# 08_EXP_CN.net
KiCad netlist of a schematic drawn in Altium Designer
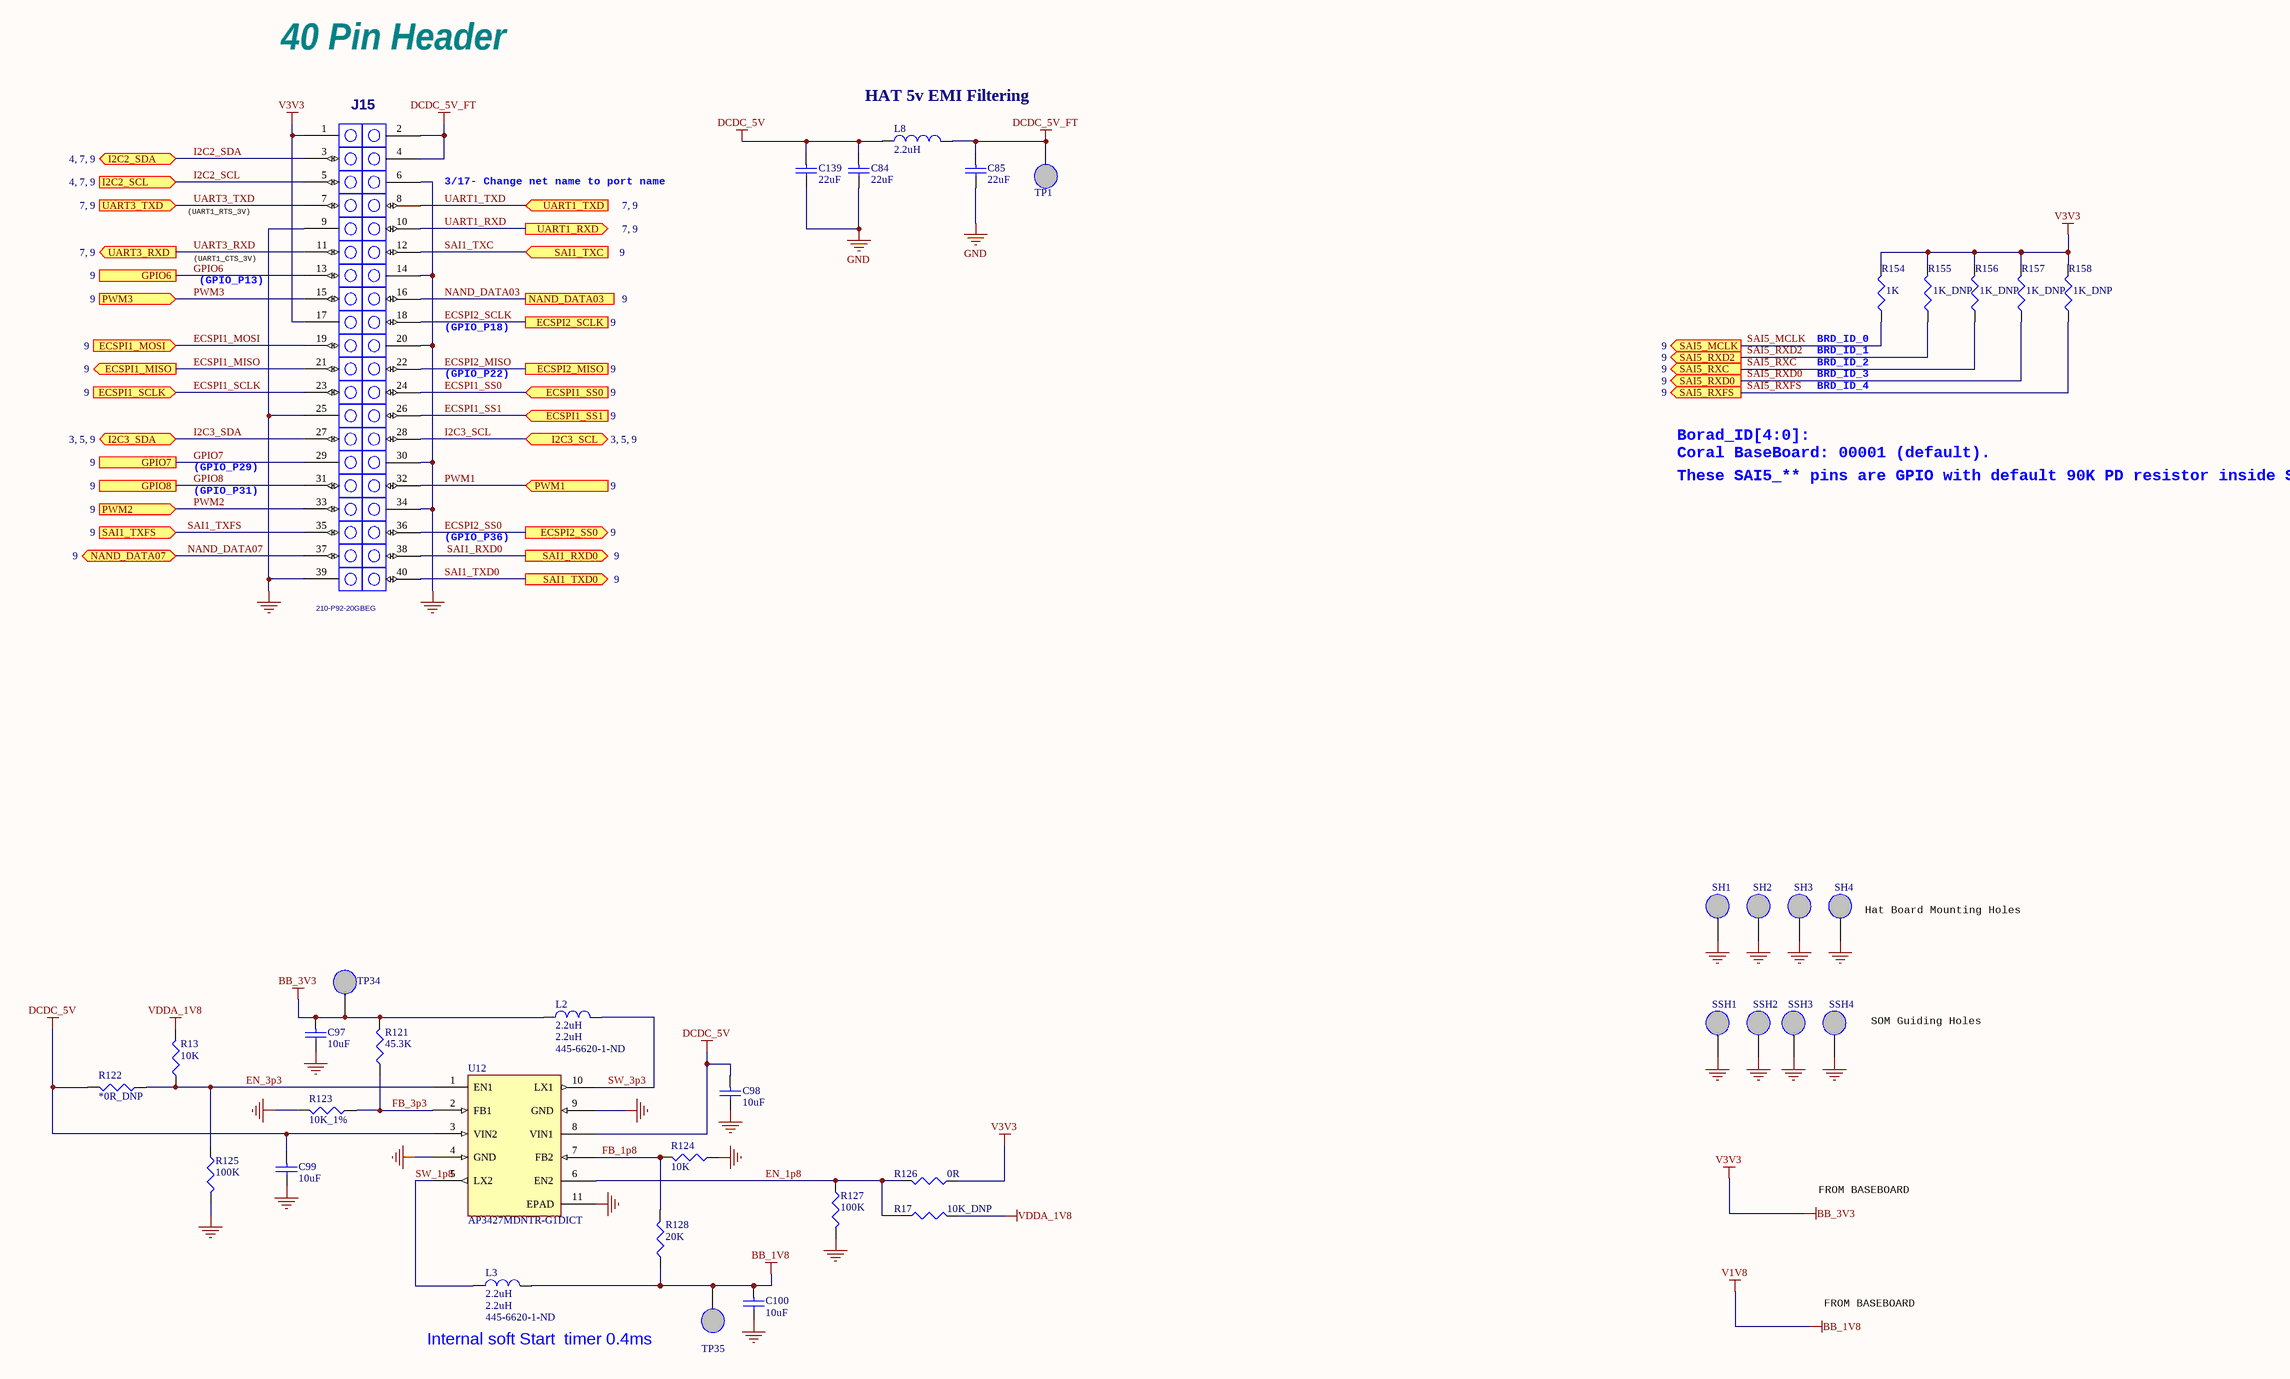
[diagram p0: 08_EXP_CN.SchDoc]

(export (version "E")
  (design (tool "Eeschema 10.0.6"))
  (components
    (comp (ref "C84")
      (value "22uF")
      (footprint "0603")
      (description "CAP CER 22UF 6.3V 10% X5R 0603")
      (fields (field (name "MPN") "CL10A226KQ8NRNE") (field (name "Comment") "22uF/10V"))
      (libsource (lib "links") (part "CAP_0603_22uF"))
    )
    (comp (ref "C85")
      (value "22uF")
      (footprint "0603")
      (description "CAP CER 22UF 6.3V 10% X5R 0603")
      (fields (field (name "MPN") "CL10A226KQ8NRNE") (field (name "Comment") "22uF/10V"))
      (libsource (lib "links") (part "CAP_0603_22uF"))
    )
    (comp (ref "C97")
      (value "10uF")
      (footprint "0402")
      (description "CAP CER 10UF 10V 20% X5R 0402")
      (fields (field (name "MPN") "CL05A106MP5NUNC") (field (name "Comment") "10uF/10V"))
      (libsource (lib "links") (part "CAP_0402_10uF"))
    )
    (comp (ref "C98")
      (value "10uF")
      (footprint "0402")
      (description "CAP CER 10UF 10V 20% X5R 0402")
      (fields (field (name "MPN") "CL05A106MP5NUNC") (field (name "Comment") "10uF/10V"))
      (libsource (lib "links") (part "CAP_0402_10uF"))
    )
    (comp (ref "C99")
      (value "10uF")
      (footprint "0402")
      (description "CAP CER 10UF 10V 20% X5R 0402")
      (fields (field (name "MPN") "CL05A106MP5NUNC") (field (name "Comment") "10uF/10V"))
      (libsource (lib "links") (part "CAP_0402_10uF"))
    )
    (comp (ref "C100")
      (value "10uF")
      (footprint "0402")
      (description "CAP CER 10UF 10V 20% X5R 0402")
      (fields (field (name "MPN") "CL05A106MP5NUNC") (field (name "Comment") "10uF/10V"))
      (libsource (lib "links") (part "CAP_0402_10uF"))
    )
    (comp (ref "C139")
      (value "22uF")
      (footprint "0603")
      (description "CAP CER 22UF 6.3V 10% X5R 0603")
      (fields (field (name "MPN") "CL10A226KQ8NRNE") (field (name "Comment") "22uF/10V"))
      (libsource (lib "links") (part "CAP_0603_22uF"))
    )
    (comp (ref "J15")
      (value "210-P92-20GBEG")
      (footprint "HTSW-120-41-G-D")
      (description "SOCKET 2X20 100-MIL STRAIGHT SMT")
      (libsource (lib "SpacePark") (part "CONN_HEADER_20x2_SMT"))
    )
    (comp (ref "L2")
      (value "2.2uH")
      (footprint "INDC2016X12L")
      (description "FIXED IND 2.2UH 1.05A 195 MOHM SMD")
      (fields
        (field (name "ALTIUM_VALUE") "2.2uH")
        (field (name "SUPPLIER PART NUMBER 1") "445-6620-1-ND")
        (field (name "MPN") "VLS201612ET-2R2M")
      )
      (libsource (lib "links") (part "INDUCTOR_VLS201612ET-2R2M"))
    )
    (comp (ref "L3")
      (value "2.2uH")
      (footprint "INDC2016X12L")
      (description "FIXED IND 2.2UH 1.05A 195 MOHM SMD")
      (fields
        (field (name "ALTIUM_VALUE") "2.2uH")
        (field (name "SUPPLIER PART NUMBER 1") "445-6620-1-ND")
        (field (name "MPN") "VLS201612ET-2R2M")
      )
      (libsource (lib "links") (part "INDUCTOR_VLS201612ET-2R2M"))
    )
    (comp (ref "L8")
      (value "2.2uH")
      (footprint "0805_PADS")
      (description "2.2?Inductor 800mA 200 mOhm Max 0805 (2012 Metric)")
      (fields (field (name "MPN") "SDTR20120H-2R2MS"))
      (libsource (lib "SpacePark") (part "INDUCTOR_2.2uH_800mA_0805"))
    )
    (comp (ref "R13")
      (value "10K")
      (footprint "0201")
      (description "RES SMD 10K OHM JUMPER 1/20W  0201")
      (fields (field (name "MPN") "ERJ-1GEF103C") (field (name "Comment") "10K_DNP"))
      (libsource (lib "links") (part "R_0201_10K"))
    )
    (comp (ref "R17")
      (value "10K_DNP")
      (footprint "0201")
      (description "RES SMD 10K OHM JUMPER 1/20W  0201")
      (fields (field (name "MPN") "ERJ-1GEF103C"))
      (libsource (lib "links") (part "R_0201_10K"))
    )
    (comp (ref "R121")
      (value "45.3K")
      (footprint "0201")
      (description "RES CHIP 45.3K 1/20W +-1%(0201)")
      (fields (field (name "MPN") "RM02FTN4532"))
      (libsource (lib "links") (part "R_0201_453K"))
    )
    (comp (ref "R122")
      (value "*0R_DNP")
      (footprint "0201")
      (description "RES SMD 0.0OHM JUMPER 1/20W 0201")
      (fields (field (name "MPN") "ERJ-1GN0R00C") (field (name "Comment") "0R"))
      (libsource (lib "links") (part "R_0201_0"))
    )
    (comp (ref "R123")
      (value "10K_1%")
      (footprint "0201")
      (description "RES SMD 10K OHM JUMPER 1/20W  0201")
      (fields (field (name "MPN") "ERJ-1GEF103C") (field (name "Comment") "10K"))
      (libsource (lib "links") (part "R_0201_10K"))
    )
    (comp (ref "R124")
      (value "10K")
      (footprint "0201")
      (description "RES SMD 10K OHM JUMPER 1/20W  0201")
      (fields (field (name "MPN") "ERJ-1GEF103C"))
      (libsource (lib "links") (part "R_0201_10K"))
    )
    (comp (ref "R125")
      (value "100K")
      (footprint "0201")
      (description "RES SMD 100K OHM JUMPER 1/20W  0201")
      (fields (field (name "MPN") "ERJ-1GEF1003C"))
      (libsource (lib "links") (part "R_0201_100K"))
    )
    (comp (ref "R126")
      (value "0R")
      (footprint "0201")
      (description "RES SMD 0.0OHM JUMPER 1/20W 0201")
      (fields (field (name "MPN") "ERJ-1GN0R00C"))
      (libsource (lib "links") (part "R_0201_0"))
    )
    (comp (ref "R127")
      (value "100K")
      (footprint "0201")
      (description "RES SMD 100K OHM JUMPER 1/20W  0201")
      (fields (field (name "MPN") "ERJ-1GEF1003C"))
      (libsource (lib "links") (part "R_0201_100K"))
    )
    (comp (ref "R128")
      (value "20K")
      (footprint "0201")
      (description "RES SMD 20K OHM 1% 1/20W 0201")
      (fields (field (name "MPN") "ERJ-1GEF2002C"))
      (libsource (lib "links") (part "R_0201_20K"))
    )
    (comp (ref "R154")
      (value "1K")
      (footprint "0201")
      (description "RES SMD 1K OHM 1% 1/20W 0201")
      (fields (field (name "MPN") "ERJ-1GEF1001C") (field (name "Comment") "1K/1%"))
      (libsource (lib "links") (part "R_0201_1K"))
    )
    (comp (ref "R155")
      (value "1K_DNP")
      (footprint "0201")
      (description "RES SMD 1K OHM 1% 1/20W 0201")
      (fields (field (name "MPN") "ERJ-1GEF1001C"))
      (libsource (lib "links") (part "R_0201_1K"))
    )
    (comp (ref "R156")
      (value "1K_DNP")
      (footprint "0201")
      (description "RES SMD 1K OHM 1% 1/20W 0201")
      (fields (field (name "MPN") "ERJ-1GEF1001C"))
      (libsource (lib "links") (part "R_0201_1K"))
    )
    (comp (ref "R157")
      (value "1K_DNP")
      (footprint "0201")
      (description "RES SMD 1K OHM 1% 1/20W 0201")
      (fields (field (name "MPN") "ERJ-1GEF1001C"))
      (libsource (lib "links") (part "R_0201_1K"))
    )
    (comp (ref "R158")
      (value "1K_DNP")
      (footprint "0201")
      (description "RES SMD 1K OHM 1% 1/20W 0201")
      (fields (field (name "MPN") "ERJ-1GEF1001C"))
      (libsource (lib "links") (part "R_0201_1K"))
    )
    (comp (ref "SH1")
      (value "TP NM")
      (footprint "hole236-110")
      (description "TEST POIN")
      (libsource (lib "links") (part "TP"))
    )
    (comp (ref "SH2")
      (value "TP NM")
      (footprint "hole236-110")
      (description "TEST POIN")
      (libsource (lib "links") (part "TP"))
    )
    (comp (ref "SH3")
      (value "TP NM")
      (footprint "hole236-110")
      (description "TEST POIN")
      (libsource (lib "links") (part "TP"))
    )
    (comp (ref "SH4")
      (value "TP NM")
      (footprint "hole236-110")
      (description "TEST POIN")
      (libsource (lib "links") (part "TP"))
    )
    (comp (ref "SSH1") (value "stand-off") (footprint "hole120-80") (libsource (lib "links") (part "TP")))
    (comp (ref "SSH2") (value "stand-off") (footprint "hole120-80") (libsource (lib "links") (part "TP")))
    (comp (ref "SSH3") (value "stand-off") (footprint "hole120-80") (libsource (lib "links") (part "TP")))
    (comp (ref "SSH4") (value "stand-off") (footprint "hole120-80") (libsource (lib "links") (part "TP")))
    (comp (ref "TP1")
      (value "TP NM")
      (footprint "TP_SMD")
      (description "TEST POIN")
      (libsource (lib "links") (part "TP"))
    )
    (comp (ref "TP34")
      (value "TP NM")
      (footprint "TP_SMD_L")
      (description "TEST POINT (Large)")
      (libsource (lib "links") (part "TP_L"))
    )
    (comp (ref "TP35")
      (value "TP NM")
      (footprint "TP_SMD_L")
      (description "TEST POINT (Large)")
      (libsource (lib "links") (part "TP_L"))
    )
    (comp (ref "U12")
      (value "AP3427MDNTR-G1DICT")
      (footprint "DFN_10_3X3")
      (description "Dual 1A, 1.5NMhz, Sync Step-Down DC/DC Converter")
      (libsource (lib "links") (part "AP3427M"))
    )
  )
  (nets
    (net (code "1") (name "/ECSPI1_MISO") (class "Default")
      (node (ref "J15") (pin "21") (pinfunction "21_21") (pintype "bidirectional"))
    )
    (net (code "2") (name "/ECSPI1_MOSI") (class "Default")
      (node (ref "J15") (pin "19") (pinfunction "19_19") (pintype "bidirectional"))
    )
    (net (code "3") (name "/ECSPI1_SCLK") (class "Default")
      (node (ref "J15") (pin "23") (pinfunction "23_23") (pintype "bidirectional"))
    )
    (net (code "4") (name "/ECSPI1_SS0") (class "Default")
      (node (ref "J15") (pin "24") (pinfunction "24_24") (pintype "bidirectional"))
    )
    (net (code "5") (name "/ECSPI1_SS1") (class "Default")
      (node (ref "J15") (pin "26") (pinfunction "26_26") (pintype "bidirectional"))
    )
    (net (code "6") (name "/ECSPI2_MISO") (class "Default")
      (node (ref "J15") (pin "22") (pinfunction "22_22") (pintype "bidirectional"))
    )
    (net (code "7") (name "/ECSPI2_SCLK") (class "Default")
      (node (ref "J15") (pin "18") (pinfunction "18_18") (pintype "bidirectional"))
    )
    (net (code "8") (name "/ECSPI2_SS0") (class "Default")
      (node (ref "J15") (pin "36") (pinfunction "36_36") (pintype "bidirectional"))
    )
    (net (code "9") (name "/EN_1p8") (class "Default")
      (node (ref "R126") (pin "2") (pintype "passive"))
      (node (ref "R127") (pin "1") (pintype "passive"))
      (node (ref "R17") (pin "1") (pintype "passive"))
      (node (ref "U12") (pin "6") (pinfunction "EN2_6") (pintype "power_in"))
    )
    (net (code "10") (name "/EN_3p3") (class "Default")
      (node (ref "R122") (pin "1") (pintype "passive"))
      (node (ref "R125") (pin "1") (pintype "passive"))
      (node (ref "R13") (pin "1") (pintype "passive"))
      (node (ref "U12") (pin "1") (pinfunction "EN1_1") (pintype "power_in"))
    )
    (net (code "11") (name "/FB_1p8") (class "Default")
      (node (ref "R124") (pin "2") (pintype "passive"))
      (node (ref "R128") (pin "2") (pintype "passive"))
      (node (ref "U12") (pin "7") (pinfunction "FB2_7") (pintype "input"))
    )
    (net (code "12") (name "/FB_3p3") (class "Default")
      (node (ref "R121") (pin "1") (pintype "passive"))
      (node (ref "R123") (pin "1") (pintype "passive"))
      (node (ref "U12") (pin "2") (pinfunction "FB1_2") (pintype "input"))
    )
    (net (code "13") (name "/GPIO6") (class "Default")
      (node (ref "J15") (pin "13") (pinfunction "13_13") (pintype "bidirectional"))
    )
    (net (code "14") (name "/GPIO7") (class "Default")
      (node (ref "J15") (pin "29") (pinfunction "29_29") (pintype "passive"))
    )
    (net (code "15") (name "/GPIO8") (class "Default")
      (node (ref "J15") (pin "31") (pinfunction "31_31") (pintype "bidirectional"))
    )
    (net (code "16") (name "/I2C2_SCL") (class "Default")
      (node (ref "J15") (pin "5") (pinfunction "5_5") (pintype "bidirectional"))
    )
    (net (code "17") (name "/I2C2_SDA") (class "Default")
      (node (ref "J15") (pin "3") (pinfunction "3_3") (pintype "bidirectional"))
    )
    (net (code "18") (name "/I2C3_SCL") (class "Default")
      (node (ref "J15") (pin "28") (pinfunction "28_28") (pintype "bidirectional"))
    )
    (net (code "19") (name "/I2C3_SDA") (class "Default")
      (node (ref "J15") (pin "27") (pinfunction "27_27") (pintype "bidirectional"))
    )
    (net (code "20") (name "/NAND_DATA03") (class "Default")
      (node (ref "J15") (pin "16") (pinfunction "16_16") (pintype "bidirectional"))
    )
    (net (code "21") (name "/NAND_DATA07") (class "Default")
      (node (ref "J15") (pin "37") (pinfunction "37_37") (pintype "bidirectional"))
    )
    (net (code "22") (name "/PWM1") (class "Default")
      (node (ref "J15") (pin "32") (pinfunction "32_32") (pintype "bidirectional"))
    )
    (net (code "23") (name "/PWM2") (class "Default")
      (node (ref "J15") (pin "33") (pinfunction "33_33") (pintype "bidirectional"))
    )
    (net (code "24") (name "/PWM3") (class "Default")
      (node (ref "J15") (pin "15") (pinfunction "15_15") (pintype "bidirectional"))
    )
    (net (code "25") (name "/SAI1_RXD0") (class "Default")
      (node (ref "J15") (pin "38") (pinfunction "38_38") (pintype "bidirectional"))
    )
    (net (code "26") (name "/SAI1_TXC") (class "Default")
      (node (ref "J15") (pin "12") (pinfunction "12_12") (pintype "bidirectional"))
    )
    (net (code "27") (name "/SAI1_TXD0") (class "Default")
      (node (ref "J15") (pin "40") (pinfunction "40_40") (pintype "bidirectional"))
    )
    (net (code "28") (name "/SAI1_TXFS") (class "Default")
      (node (ref "J15") (pin "35") (pinfunction "35_35") (pintype "bidirectional"))
    )
    (net (code "29") (name "/SAI5_MCLK") (class "Default") (node (ref "R154") (pin "1") (pintype "passive")))
    (net (code "30") (name "/SAI5_RXC") (class "Default") (node (ref "R156") (pin "1") (pintype "passive")))
    (net (code "31") (name "/SAI5_RXD0") (class "Default") (node (ref "R157") (pin "1") (pintype "passive")))
    (net (code "32") (name "/SAI5_RXD2") (class "Default") (node (ref "R155") (pin "1") (pintype "passive")))
    (net (code "33") (name "/SAI5_RXFS") (class "Default") (node (ref "R158") (pin "1") (pintype "passive")))
    (net (code "34") (name "/SW_1p8") (class "Default")
      (node (ref "L3") (pin "1") (pinfunction "1_1") (pintype "passive"))
      (node (ref "U12") (pin "5") (pinfunction "LX2_5") (pintype "output"))
    )
    (net (code "35") (name "/SW_3p3") (class "Default")
      (node (ref "L2") (pin "2") (pinfunction "2_2") (pintype "passive"))
      (node (ref "U12") (pin "10") (pinfunction "LX1_10") (pintype "output"))
    )
    (net (code "36") (name "/UART1_RXD") (class "Default")
      (node (ref "J15") (pin "10") (pinfunction "10_10") (pintype "bidirectional"))
    )
    (net (code "37") (name "/UART1_TXD") (class "Default")
      (node (ref "J15") (pin "8") (pinfunction "8_8") (pintype "bidirectional"))
    )
    (net (code "38") (name "/UART3_RXD") (class "Default")
      (node (ref "J15") (pin "11") (pinfunction "11_11") (pintype "bidirectional"))
    )
    (net (code "39") (name "/UART3_TXD") (class "Default")
      (node (ref "J15") (pin "7") (pinfunction "7_7") (pintype "bidirectional"))
    )
    (net (code "40") (name "BB_1V8") (class "Default")
      (node (ref "C100") (pin "1") (pinfunction "1_1") (pintype "passive"))
      (node (ref "L3") (pin "2") (pinfunction "2_2") (pintype "passive"))
      (node (ref "R128") (pin "1") (pintype "passive"))
      (node (ref "TP35") (pin "1") (pinfunction "1_1") (pintype "passive"))
    )
    (net (code "41") (name "BB_3V3") (class "Default")
      (node (ref "C97") (pin "1") (pinfunction "1_1") (pintype "passive"))
      (node (ref "J15") (pin "1") (pinfunction "1_1") (pintype "passive"))
      (node (ref "J15") (pin "17") (pinfunction "17_17") (pintype "passive"))
      (node (ref "L2") (pin "1") (pinfunction "1_1") (pintype "passive"))
      (node (ref "R121") (pin "2") (pintype "passive"))
      (node (ref "R126") (pin "1") (pintype "passive"))
      (node (ref "R154") (pin "2") (pintype "passive"))
      (node (ref "R155") (pin "2") (pintype "passive"))
      (node (ref "R156") (pin "2") (pintype "passive"))
      (node (ref "R157") (pin "2") (pintype "passive"))
      (node (ref "R158") (pin "2") (pintype "passive"))
      (node (ref "TP34") (pin "1") (pinfunction "1_1") (pintype "passive"))
    )
    (net (code "42") (name "DCDC_5V") (class "Default")
      (node (ref "C139") (pin "1") (pinfunction "1_1") (pintype "passive"))
      (node (ref "C84") (pin "1") (pinfunction "1_1") (pintype "passive"))
      (node (ref "C98") (pin "1") (pinfunction "1_1") (pintype "passive"))
      (node (ref "C99") (pin "1") (pinfunction "1_1") (pintype "passive"))
      (node (ref "L8") (pin "1") (pinfunction "1_1") (pintype "passive"))
      (node (ref "R122") (pin "2") (pintype "passive"))
      (node (ref "U12") (pin "3") (pinfunction "VIN2_3") (pintype "input"))
      (node (ref "U12") (pin "8") (pinfunction "VIN1_8") (pintype "power_in"))
    )
    (net (code "43") (name "DCDC_5V_FT") (class "Default")
      (node (ref "C85") (pin "1") (pinfunction "1_1") (pintype "passive"))
      (node (ref "J15") (pin "2") (pinfunction "2_2") (pintype "passive"))
      (node (ref "J15") (pin "4") (pinfunction "4_4") (pintype "passive"))
      (node (ref "L8") (pin "2") (pinfunction "2_2") (pintype "passive"))
      (node (ref "TP1") (pin "1") (pinfunction "1_1") (pintype "passive"))
    )
    (net (code "44") (name "GND") (class "Default")
      (node (ref "C100") (pin "2") (pinfunction "2_2") (pintype "passive"))
      (node (ref "C139") (pin "2") (pinfunction "2_2") (pintype "passive"))
      (node (ref "C84") (pin "2") (pinfunction "2_2") (pintype "passive"))
      (node (ref "C85") (pin "2") (pinfunction "2_2") (pintype "passive"))
      (node (ref "C97") (pin "2") (pinfunction "2_2") (pintype "passive"))
      (node (ref "C98") (pin "2") (pinfunction "2_2") (pintype "passive"))
      (node (ref "C99") (pin "2") (pinfunction "2_2") (pintype "passive"))
      (node (ref "J15") (pin "14") (pinfunction "14_14") (pintype "passive"))
      (node (ref "J15") (pin "20") (pinfunction "20_20") (pintype "passive"))
      (node (ref "J15") (pin "25") (pinfunction "25_25") (pintype "passive"))
      (node (ref "J15") (pin "30") (pinfunction "30_30") (pintype "passive"))
      (node (ref "J15") (pin "34") (pinfunction "34_34") (pintype "passive"))
      (node (ref "J15") (pin "39") (pinfunction "39_39") (pintype "passive"))
      (node (ref "J15") (pin "6") (pinfunction "6_6") (pintype "passive"))
      (node (ref "J15") (pin "9") (pinfunction "9_9") (pintype "passive"))
      (node (ref "R123") (pin "2") (pintype "passive"))
      (node (ref "R124") (pin "1") (pintype "passive"))
      (node (ref "R125") (pin "2") (pintype "passive"))
      (node (ref "R127") (pin "2") (pintype "passive"))
      (node (ref "SH1") (pin "1") (pinfunction "1_1") (pintype "passive"))
      (node (ref "SH2") (pin "1") (pinfunction "1_1") (pintype "passive"))
      (node (ref "SH3") (pin "1") (pinfunction "1_1") (pintype "passive"))
      (node (ref "SH4") (pin "1") (pinfunction "1_1") (pintype "passive"))
      (node (ref "SSH1") (pin "1") (pinfunction "1_1") (pintype "passive"))
      (node (ref "SSH2") (pin "1") (pinfunction "1_1") (pintype "passive"))
      (node (ref "SSH3") (pin "1") (pinfunction "1_1") (pintype "passive"))
      (node (ref "SSH4") (pin "1") (pinfunction "1_1") (pintype "passive"))
      (node (ref "U12") (pin "11") (pinfunction "EPAD_11") (pintype "power_in"))
      (node (ref "U12") (pin "4") (pinfunction "GND_4") (pintype "input"))
      (node (ref "U12") (pin "9") (pinfunction "GND_9") (pintype "input"))
    )
    (net (code "45") (name "VDDA_1V8") (class "Default")
      (node (ref "R13") (pin "2") (pintype "passive"))
      (node (ref "R17") (pin "2") (pintype "passive"))
    )
  )
)
